# BLE.net
KiCad netlist of a schematic drawn in Altium Designer
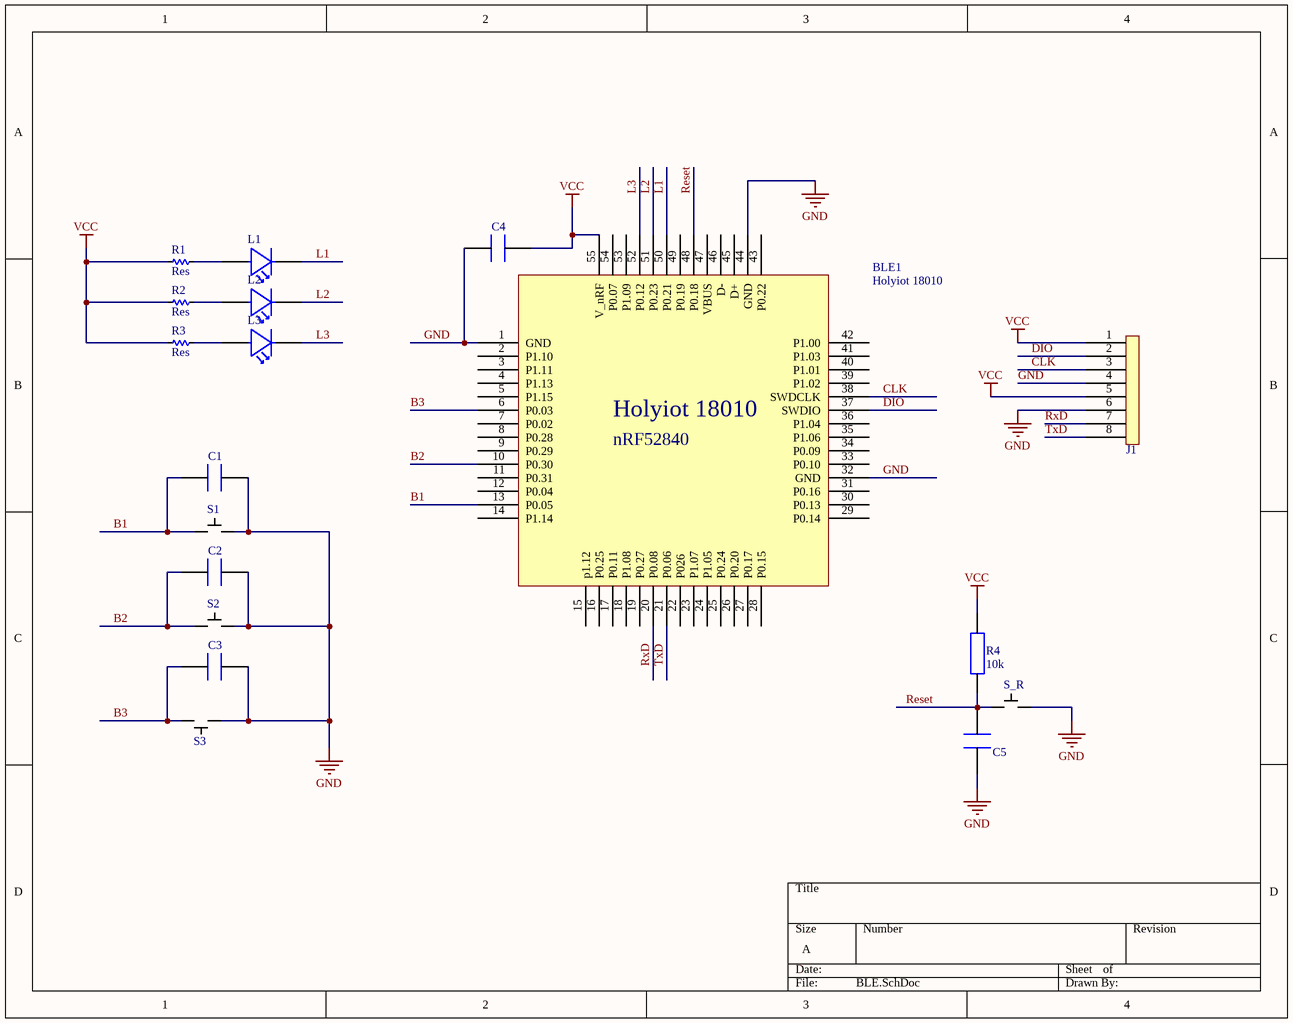
[diagram p0: BLE.SchDoc]

(export (version "E")
  (design (tool "Eeschema 10.0.6"))
  (components
    (comp (ref "BLE1")
      (value "Holyiot 18010")
      (footprint "Holyiot 18010")
      (libsource (lib "LuongTanDat") (part "Holyiot 18010"))
    )
    (comp (ref "C1") (value "Cap") (footprint "CAP-0805") (libsource (lib "LuongTanDat") (part "Cap")))
    (comp (ref "C2") (value "Cap") (footprint "CAP-0805") (libsource (lib "LuongTanDat") (part "Cap")))
    (comp (ref "C3") (value "Cap") (footprint "CAP-0805") (libsource (lib "LuongTanDat") (part "Cap")))
    (comp (ref "C4") (value "Cap") (footprint "CAP-0805") (libsource (lib "LuongTanDat") (part "Cap")))
    (comp (ref "C5") (value "Cap") (footprint "CAP-0805") (libsource (lib "LuongTanDat") (part "Cap")))
    (comp (ref "J1") (value "JP_8") (footprint "JP_8") (libsource (lib "LuongTanDat") (part "JP_8")))
    (comp (ref "L1") (value "LED") (footprint "LED0805") (libsource (lib "LuongTanDat") (part "LED")))
    (comp (ref "L2") (value "LED") (footprint "LED0805") (libsource (lib "LuongTanDat") (part "LED")))
    (comp (ref "L3") (value "LED") (footprint "LED0805") (libsource (lib "LuongTanDat") (part "LED")))
    (comp (ref "R1")
      (value "Res")
      (footprint "RES-SMD-0805")
      (description "Resistor")
      (fields
        (field (name "MANUFACTURER") "Generic Components")
        (field (name "PUBLISHER") "Altium Hobart Technology Centre")
      )
      (libsource (lib "LIBRARY") (part "Res-SMD"))
    )
    (comp (ref "R2")
      (value "Res")
      (footprint "RES-SMD-0805")
      (description "Resistor")
      (fields
        (field (name "MANUFACTURER") "Generic Components")
        (field (name "PUBLISHER") "Altium Hobart Technology Centre")
      )
      (libsource (lib "LIBRARY") (part "Res-SMD"))
    )
    (comp (ref "R3")
      (value "Res")
      (footprint "RES-SMD-0805")
      (description "Resistor")
      (fields
        (field (name "MANUFACTURER") "Generic Components")
        (field (name "PUBLISHER") "Altium Hobart Technology Centre")
      )
      (libsource (lib "LIBRARY") (part "Res-SMD"))
    )
    (comp (ref "R4")
      (value "10k")
      (footprint "RES0805")
      (description "điện trở size nhỏ")
      (libsource (lib "LuongTanDat") (part "RES"))
    )
    (comp (ref "S1")
      (value "Button")
      (footprint "button_smd")
      (libsource (lib "LuongTanDat") (part "Button"))
    )
    (comp (ref "S2")
      (value "Button")
      (footprint "button_smd")
      (libsource (lib "LuongTanDat") (part "Button"))
    )
    (comp (ref "S3")
      (value "Button")
      (footprint "button_smd")
      (libsource (lib "LuongTanDat") (part "Button"))
    )
    (comp (ref "S_R")
      (value "Button")
      (footprint "button_smd")
      (libsource (lib "LuongTanDat") (part "Button"))
    )
  )
  (nets
    (net (code "1") (name "/B1") (class "Default")
      (node (ref "BLE1") (pin "13") (pinfunction "P0.05_13") (pintype "passive"))
      (node (ref "C1") (pin "1") (pinfunction "1_1") (pintype "passive"))
      (node (ref "S1") (pin "1") (pinfunction "0_1") (pintype "passive"))
    )
    (net (code "2") (name "/B2") (class "Default")
      (node (ref "BLE1") (pin "10") (pinfunction "P0.30_10") (pintype "passive"))
      (node (ref "C2") (pin "1") (pinfunction "1_1") (pintype "passive"))
      (node (ref "S2") (pin "1") (pinfunction "0_1") (pintype "passive"))
    )
    (net (code "3") (name "/B3") (class "Default")
      (node (ref "BLE1") (pin "6") (pinfunction "P0.03_6") (pintype "passive"))
      (node (ref "C3") (pin "1") (pinfunction "1_1") (pintype "passive"))
      (node (ref "S3") (pin "2") (pinfunction "10_2") (pintype "passive"))
    )
    (net (code "4") (name "/CLK") (class "Default")
      (node (ref "BLE1") (pin "38") (pinfunction "SWDCLK_38") (pintype "passive"))
      (node (ref "J1") (pin "3") (pinfunction "3_3") (pintype "passive"))
    )
    (net (code "5") (name "/DIO") (class "Default")
      (node (ref "BLE1") (pin "37") (pinfunction "SWDIO_37") (pintype "passive"))
      (node (ref "J1") (pin "2") (pinfunction "2_2") (pintype "passive"))
    )
    (net (code "6") (name "/L1") (class "Default")
      (node (ref "BLE1") (pin "50") (pinfunction "P0.21_50") (pintype "passive"))
      (node (ref "L1") (pin "C") (pinfunction "2_C") (pintype "passive"))
    )
    (net (code "7") (name "/L2") (class "Default")
      (node (ref "BLE1") (pin "51") (pinfunction "P0.23_51") (pintype "passive"))
      (node (ref "L2") (pin "C") (pinfunction "2_C") (pintype "passive"))
    )
    (net (code "8") (name "/L3") (class "Default")
      (node (ref "BLE1") (pin "52") (pinfunction "P0.12_52") (pintype "passive"))
      (node (ref "L3") (pin "C") (pinfunction "2_C") (pintype "passive"))
    )
    (net (code "9") (name "/Reset") (class "Default")
      (node (ref "BLE1") (pin "48") (pinfunction "P0.18_48") (pintype "passive"))
      (node (ref "C5") (pin "2") (pinfunction "2_2") (pintype "passive"))
      (node (ref "R4") (pin "1") (pinfunction "1_1") (pintype "passive"))
      (node (ref "S_R") (pin "1") (pinfunction "0_1") (pintype "passive"))
    )
    (net (code "10") (name "/RxD") (class "Default")
      (node (ref "BLE1") (pin "20") (pinfunction "P0.08_20") (pintype "passive"))
      (node (ref "J1") (pin "7") (pinfunction "7_7") (pintype "passive"))
    )
    (net (code "11") (name "/TxD") (class "Default")
      (node (ref "BLE1") (pin "21") (pinfunction "P0.06_21") (pintype "passive"))
      (node (ref "J1") (pin "8") (pinfunction "8_8") (pintype "passive"))
    )
    (net (code "12") (name "GND") (class "Default")
      (node (ref "BLE1") (pin "1") (pinfunction "GND_1") (pintype "passive"))
      (node (ref "BLE1") (pin "32") (pinfunction "GND_32") (pintype "passive"))
      (node (ref "BLE1") (pin "44") (pinfunction "GND_44") (pintype "passive"))
      (node (ref "C1") (pin "2") (pinfunction "2_2") (pintype "passive"))
      (node (ref "C2") (pin "2") (pinfunction "2_2") (pintype "passive"))
      (node (ref "C3") (pin "2") (pinfunction "2_2") (pintype "passive"))
      (node (ref "C4") (pin "1") (pinfunction "1_1") (pintype "passive"))
      (node (ref "C5") (pin "1") (pinfunction "1_1") (pintype "passive"))
      (node (ref "J1") (pin "4") (pinfunction "4_4") (pintype "passive"))
      (node (ref "J1") (pin "6") (pinfunction "6_6") (pintype "passive"))
      (node (ref "S1") (pin "2") (pinfunction "10_2") (pintype "passive"))
      (node (ref "S2") (pin "2") (pinfunction "10_2") (pintype "passive"))
      (node (ref "S3") (pin "1") (pinfunction "0_1") (pintype "passive"))
      (node (ref "S_R") (pin "2") (pinfunction "10_2") (pintype "passive"))
    )
    (net (code "13") (name "Net-(L1-1)") (class "Default")
      (node (ref "L1") (pin "A") (pinfunction "1_A") (pintype "passive"))
      (node (ref "R1") (pin "1") (pinfunction "1_1") (pintype "passive"))
    )
    (net (code "14") (name "Net-(L2-1)") (class "Default")
      (node (ref "L2") (pin "A") (pinfunction "1_A") (pintype "passive"))
      (node (ref "R2") (pin "1") (pinfunction "1_1") (pintype "passive"))
    )
    (net (code "15") (name "Net-(L3-1)") (class "Default")
      (node (ref "L3") (pin "A") (pinfunction "1_A") (pintype "passive"))
      (node (ref "R3") (pin "1") (pinfunction "1_1") (pintype "passive"))
    )
    (net (code "16") (name "VCC") (class "Default")
      (node (ref "BLE1") (pin "55") (pinfunction "V_nRF_55") (pintype "passive"))
      (node (ref "C4") (pin "2") (pinfunction "2_2") (pintype "passive"))
      (node (ref "J1") (pin "1") (pinfunction "1_1") (pintype "passive"))
      (node (ref "J1") (pin "5") (pinfunction "5_5") (pintype "passive"))
      (node (ref "R1") (pin "2") (pinfunction "2_2") (pintype "passive"))
      (node (ref "R2") (pin "2") (pinfunction "2_2") (pintype "passive"))
      (node (ref "R3") (pin "2") (pinfunction "2_2") (pintype "passive"))
      (node (ref "R4") (pin "2") (pinfunction "2_2") (pintype "passive"))
    )
    (net (code "17") (name "unconnected-(BLE1-D+-Pad45)") (class "Default")
      (node (ref "BLE1") (pin "45") (pinfunction "D+_45") (pintype "passive"))
    )
    (net (code "18") (name "unconnected-(BLE1-D--Pad46)") (class "Default")
      (node (ref "BLE1") (pin "46") (pinfunction "D-_46") (pintype "passive"))
    )
    (net (code "19") (name "unconnected-(BLE1-P0.02-Pad7)") (class "Default")
      (node (ref "BLE1") (pin "7") (pinfunction "P0.02_7") (pintype "passive"))
    )
    (net (code "20") (name "unconnected-(BLE1-P0.04-Pad12)") (class "Default")
      (node (ref "BLE1") (pin "12") (pinfunction "P0.04_12") (pintype "passive"))
    )
    (net (code "21") (name "unconnected-(BLE1-P0.07-Pad54)") (class "Default")
      (node (ref "BLE1") (pin "54") (pinfunction "P0.07_54") (pintype "passive"))
    )
    (net (code "22") (name "unconnected-(BLE1-P0.09-Pad34)") (class "Default")
      (node (ref "BLE1") (pin "34") (pinfunction "P0.09_34") (pintype "passive"))
    )
    (net (code "23") (name "unconnected-(BLE1-P0.10-Pad33)") (class "Default")
      (node (ref "BLE1") (pin "33") (pinfunction "P0.10_33") (pintype "passive"))
    )
    (net (code "24") (name "unconnected-(BLE1-P0.11-Pad17)") (class "Default")
      (node (ref "BLE1") (pin "17") (pinfunction "P0.11_17") (pintype "passive"))
    )
    (net (code "25") (name "unconnected-(BLE1-P0.13-Pad30)") (class "Default")
      (node (ref "BLE1") (pin "30") (pinfunction "P0.13_30") (pintype "passive"))
    )
    (net (code "26") (name "unconnected-(BLE1-P0.14-Pad29)") (class "Default")
      (node (ref "BLE1") (pin "29") (pinfunction "P0.14_29") (pintype "passive"))
    )
    (net (code "27") (name "unconnected-(BLE1-P0.15-Pad28)") (class "Default")
      (node (ref "BLE1") (pin "28") (pinfunction "P0.15_28") (pintype "passive"))
    )
    (net (code "28") (name "unconnected-(BLE1-P0.16-Pad31)") (class "Default")
      (node (ref "BLE1") (pin "31") (pinfunction "P0.16_31") (pintype "passive"))
    )
    (net (code "29") (name "unconnected-(BLE1-P0.17-Pad27)") (class "Default")
      (node (ref "BLE1") (pin "27") (pinfunction "P0.17_27") (pintype "passive"))
    )
    (net (code "30") (name "unconnected-(BLE1-P0.19-Pad49)") (class "Default")
      (node (ref "BLE1") (pin "49") (pinfunction "P0.19_49") (pintype "passive"))
    )
    (net (code "31") (name "unconnected-(BLE1-P0.20-Pad26)") (class "Default")
      (node (ref "BLE1") (pin "26") (pinfunction "P0.20_26") (pintype "passive"))
    )
    (net (code "32") (name "unconnected-(BLE1-P0.22-Pad43)") (class "Default")
      (node (ref "BLE1") (pin "43") (pinfunction "P0.22_43") (pintype "passive"))
    )
    (net (code "33") (name "unconnected-(BLE1-P0.24-Pad25)") (class "Default")
      (node (ref "BLE1") (pin "25") (pinfunction "P0.24_25") (pintype "passive"))
    )
    (net (code "34") (name "unconnected-(BLE1-P0.25-Pad16)") (class "Default")
      (node (ref "BLE1") (pin "16") (pinfunction "P0.25_16") (pintype "passive"))
    )
    (net (code "35") (name "unconnected-(BLE1-P0.27-Pad19)") (class "Default")
      (node (ref "BLE1") (pin "19") (pinfunction "P0.27_19") (pintype "passive"))
    )
    (net (code "36") (name "unconnected-(BLE1-P0.28-Pad8)") (class "Default")
      (node (ref "BLE1") (pin "8") (pinfunction "P0.28_8") (pintype "passive"))
    )
    (net (code "37") (name "unconnected-(BLE1-P0.29-Pad9)") (class "Default")
      (node (ref "BLE1") (pin "9") (pinfunction "P0.29_9") (pintype "passive"))
    )
    (net (code "38") (name "unconnected-(BLE1-P0.31-Pad11)") (class "Default")
      (node (ref "BLE1") (pin "11") (pinfunction "P0.31_11") (pintype "passive"))
    )
    (net (code "39") (name "unconnected-(BLE1-P1.00-Pad42)") (class "Default")
      (node (ref "BLE1") (pin "42") (pinfunction "P1.00_42") (pintype "passive"))
    )
    (net (code "40") (name "unconnected-(BLE1-P1.01-Pad40)") (class "Default")
      (node (ref "BLE1") (pin "40") (pinfunction "P1.01_40") (pintype "passive"))
    )
    (net (code "41") (name "unconnected-(BLE1-P1.02-Pad39)") (class "Default")
      (node (ref "BLE1") (pin "39") (pinfunction "P1.02_39") (pintype "passive"))
    )
    (net (code "42") (name "unconnected-(BLE1-P1.03-Pad41)") (class "Default")
      (node (ref "BLE1") (pin "41") (pinfunction "P1.03_41") (pintype "passive"))
    )
    (net (code "43") (name "unconnected-(BLE1-P1.04-Pad36)") (class "Default")
      (node (ref "BLE1") (pin "36") (pinfunction "P1.04_36") (pintype "passive"))
    )
    (net (code "44") (name "unconnected-(BLE1-P1.05-Pad24)") (class "Default")
      (node (ref "BLE1") (pin "24") (pinfunction "P1.05_24") (pintype "passive"))
    )
    (net (code "45") (name "unconnected-(BLE1-P1.06-Pad35)") (class "Default")
      (node (ref "BLE1") (pin "35") (pinfunction "P1.06_35") (pintype "passive"))
    )
    (net (code "46") (name "unconnected-(BLE1-P1.07-Pad23)") (class "Default")
      (node (ref "BLE1") (pin "23") (pinfunction "P1.07_23") (pintype "passive"))
    )
    (net (code "47") (name "unconnected-(BLE1-P1.08-Pad18)") (class "Default")
      (node (ref "BLE1") (pin "18") (pinfunction "P1.08_18") (pintype "passive"))
    )
    (net (code "48") (name "unconnected-(BLE1-P1.09-Pad53)") (class "Default")
      (node (ref "BLE1") (pin "53") (pinfunction "P1.09_53") (pintype "passive"))
    )
    (net (code "49") (name "unconnected-(BLE1-P1.10-Pad2)") (class "Default")
      (node (ref "BLE1") (pin "2") (pinfunction "P1.10_2") (pintype "passive"))
    )
    (net (code "50") (name "unconnected-(BLE1-P1.11-Pad3)") (class "Default")
      (node (ref "BLE1") (pin "3") (pinfunction "P1.11_3") (pintype "passive"))
    )
    (net (code "51") (name "unconnected-(BLE1-P1.13-Pad4)") (class "Default")
      (node (ref "BLE1") (pin "4") (pinfunction "P1.13_4") (pintype "passive"))
    )
    (net (code "52") (name "unconnected-(BLE1-P1.14-Pad14)") (class "Default")
      (node (ref "BLE1") (pin "14") (pinfunction "P1.14_14") (pintype "passive"))
    )
    (net (code "53") (name "unconnected-(BLE1-P1.15-Pad5)") (class "Default")
      (node (ref "BLE1") (pin "5") (pinfunction "P1.15_5") (pintype "passive"))
    )
    (net (code "54") (name "unconnected-(BLE1-P026-Pad22)") (class "Default")
      (node (ref "BLE1") (pin "22") (pinfunction "P026_22") (pintype "passive"))
    )
    (net (code "55") (name "unconnected-(BLE1-VBUS-Pad47)") (class "Default")
      (node (ref "BLE1") (pin "47") (pinfunction "VBUS_47") (pintype "passive"))
    )
    (net (code "56") (name "unconnected-(BLE1-p1.12-Pad15)") (class "Default")
      (node (ref "BLE1") (pin "15") (pinfunction "p1.12_15") (pintype "passive"))
    )
  )
)
